# IC_Schema.net
KiCad netlist of a schematic drawn in Altium Designer
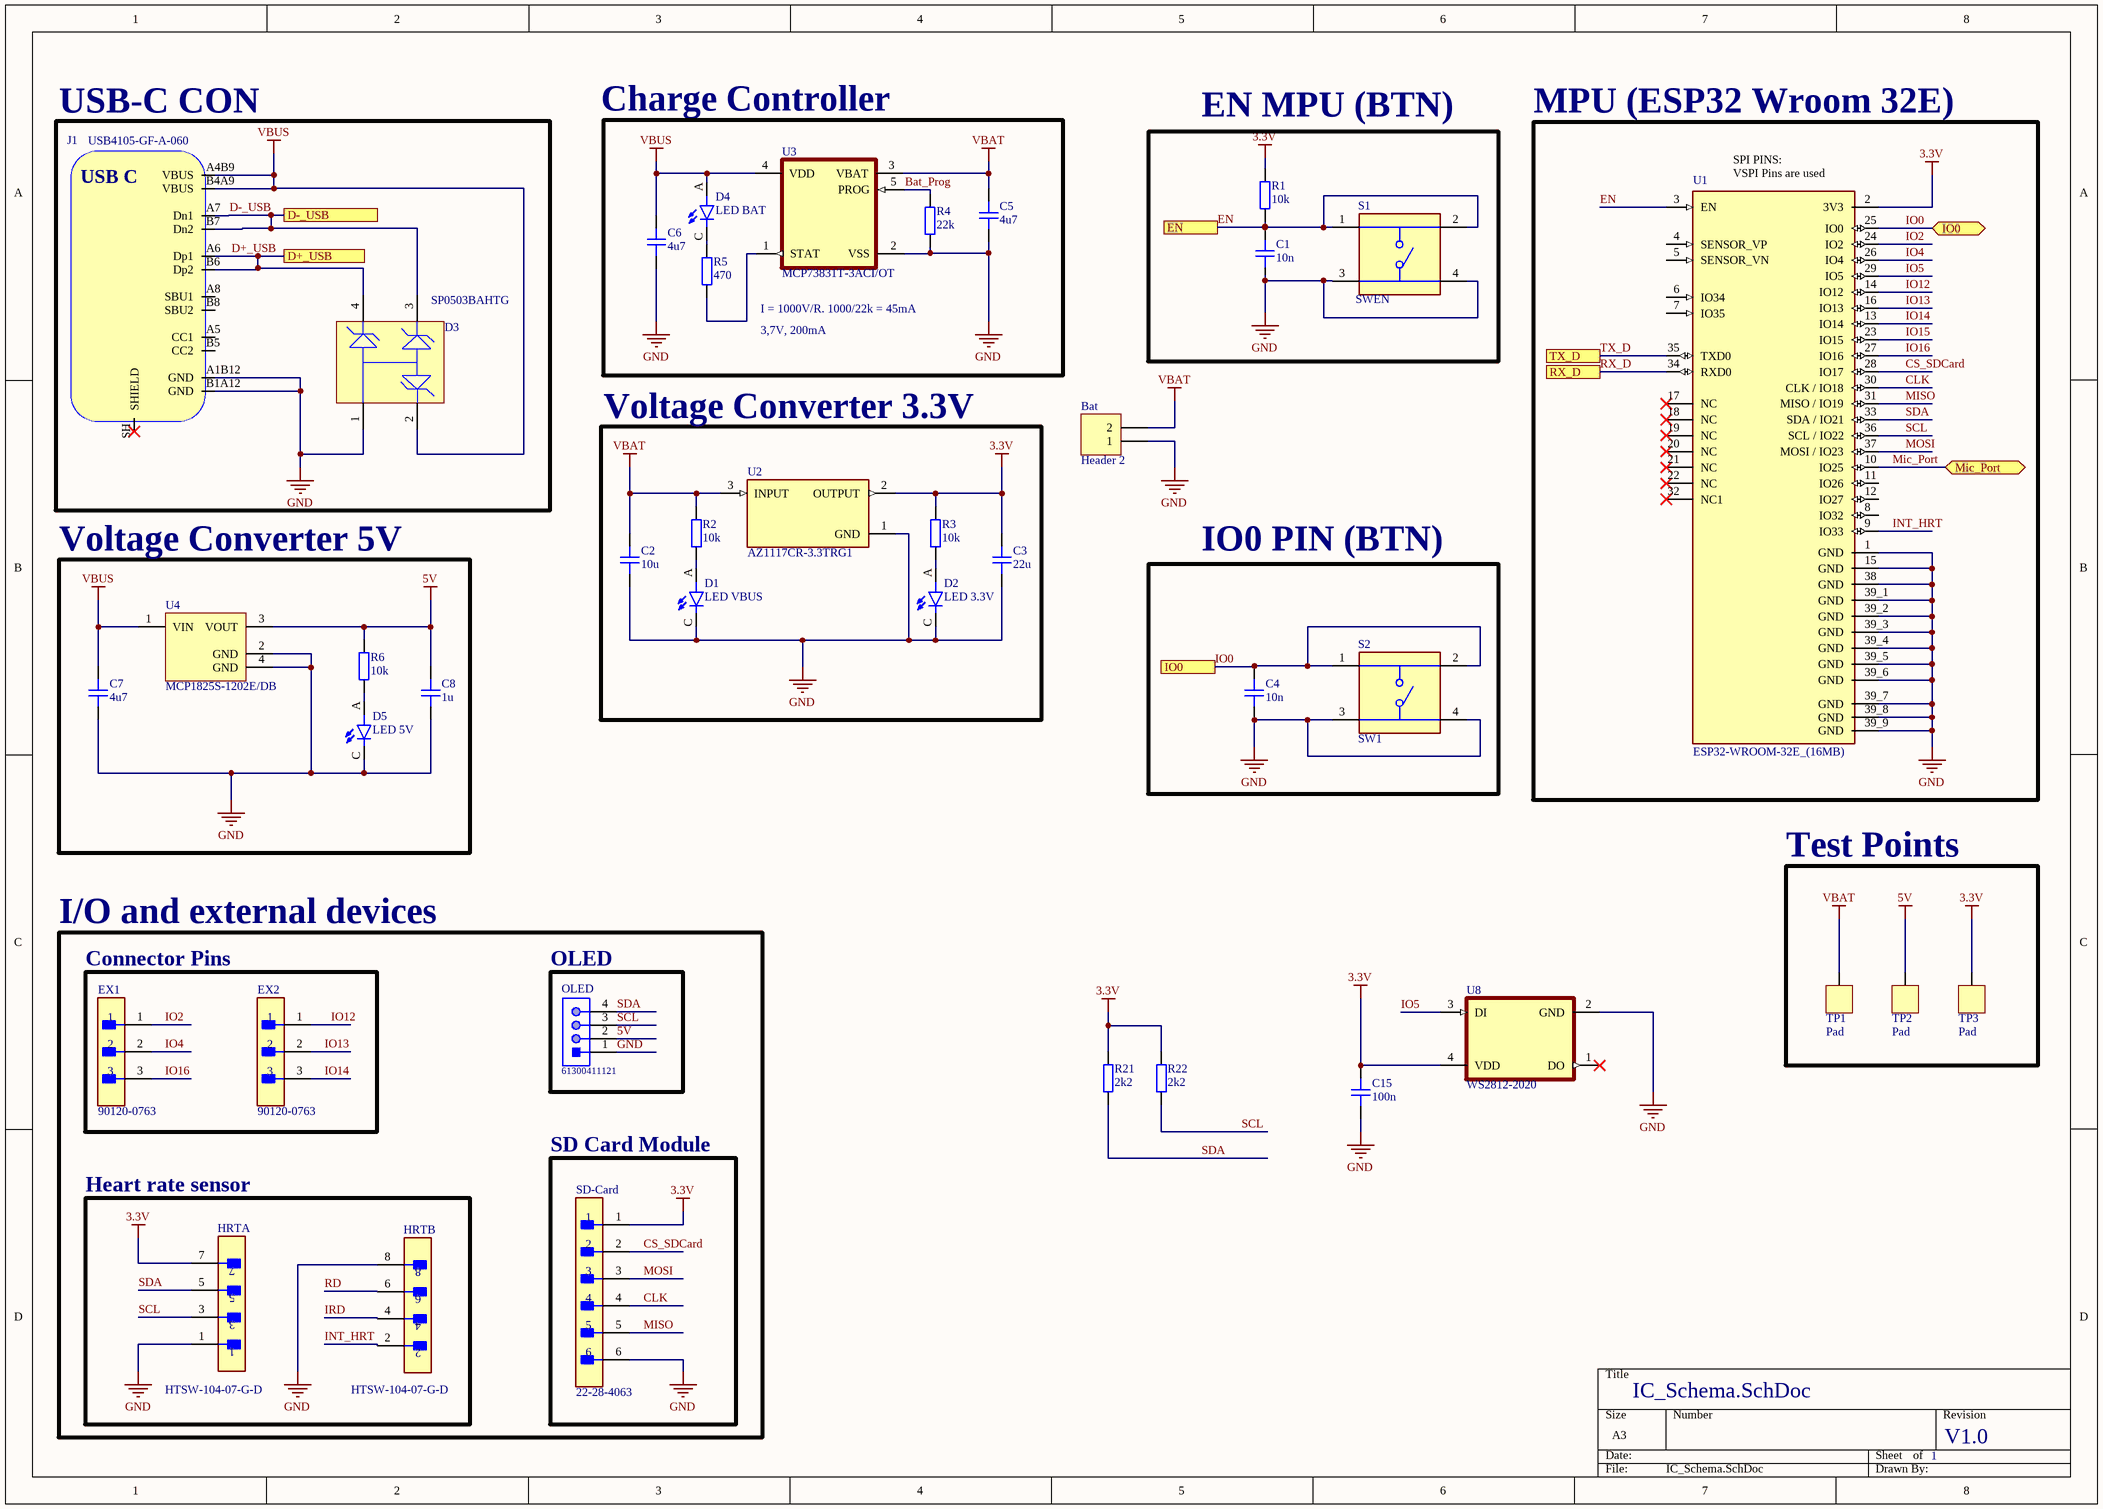
[diagram p0: IC_Schema.SchDoc]

(export (version "E")
  (design (tool "Eeschema 10.0.6"))
  (components
    (comp (ref "Bat")
      (value "Header 2")
      (footprint "HDR1X2")
      (description "Header, 2-Pin")
      (fields (field (name "PUBLISHER") "Altium Limited"))
      (libsource (lib "Miscellaneous Connectors") (part "Header 2"))
    )
    (comp (ref "C1")
      (value "10n")
      (footprint "CAP_1206")
      (description "Capacitor SMD 1206 50V")
      (libsource (lib "Schem_Lib_DaanHeetkamp.") (part "CAP_1206_50V"))
    )
    (comp (ref "C2")
      (value "10u")
      (footprint "CAP_1206")
      (description "Capacitor SMD 1206 50V")
      (libsource (lib "Schem_Lib_DaanHeetkamp.") (part "CAP_1206_50V"))
    )
    (comp (ref "C3")
      (value "22u")
      (footprint "CAP_1206")
      (description "Capacitor SMD 1206 50V")
      (libsource (lib "Schem_Lib_DaanHeetkamp.") (part "CAP_1206_50V"))
    )
    (comp (ref "C4")
      (value "10n")
      (footprint "CAP_1206")
      (description "Capacitor SMD 1206 50V")
      (libsource (lib "Schem_Lib_DaanHeetkamp.") (part "CAP_1206_50V"))
    )
    (comp (ref "C5")
      (value "4u7")
      (footprint "CAP_1206")
      (description "Capacitor SMD 1206 50V")
      (libsource (lib "Schem_Lib_DaanHeetkamp.") (part "CAP_1206_50V"))
    )
    (comp (ref "C6")
      (value "4u7")
      (footprint "CAP_1206")
      (description "Capacitor SMD 1206 50V")
      (libsource (lib "Schem_Lib_DaanHeetkamp.") (part "CAP_1206_50V"))
    )
    (comp (ref "C7")
      (value "4u7")
      (footprint "CAP_1206")
      (description "Capacitor SMD 1206 50V")
      (libsource (lib "Schem_Lib_DaanHeetkamp.") (part "CAP_1206_50V"))
    )
    (comp (ref "C8")
      (value "1u")
      (footprint "CAP_1206")
      (description "Capacitor SMD 1206 50V")
      (libsource (lib "Schem_Lib_DaanHeetkamp.") (part "CAP_1206_50V"))
    )
    (comp (ref "C15")
      (value "100n")
      (footprint "CAP_1206")
      (description "Capacitor SMD 1206 50V")
      (libsource (lib "Schem_Lib_DaanHeetkamp.") (part "CAP_1206_50V"))
    )
    (comp (ref "D1")
      (value "LED VBUS")
      (footprint "PCB_Lib_DaanHeetkamp:LED_1206")
      (description "Yellow 587nm LED Indication - Discrete 2V 1206 _3216 Metric_")
      (fields (field (name "MF") "Lite-On Inc.") (field (name "MP") "LTST-C230KSKT"))
      (libsource (lib "Schem_Lib_DaanHeetkamp.") (part "LED - 1206"))
    )
    (comp (ref "D2")
      (value "LED 3.3V")
      (footprint "PCB_Lib_DaanHeetkamp:LED_1206")
      (description "Yellow 587nm LED Indication - Discrete 2V 1206 _3216 Metric_")
      (fields (field (name "MF") "Lite-On Inc.") (field (name "MP") "LTST-C230KSKT"))
      (libsource (lib "Schem_Lib_DaanHeetkamp.") (part "LED - 1206"))
    )
    (comp (ref "D3")
      (value "SP0503BAHTG")
      (footprint "LFUS-SOT143-4_V")
      (description "TVS Diode Array, 30 pF, 30 KV, -40 to 85 degC, 4-Pin SOT143, RoHS, Tape and Reel")
      (fields (field (name "MANUFACTURER") "Littelfuse"))
      (libsource (lib "Altium Content Vault") (part "LFUS-SP0503BAHTG-SOT143-4"))
    )
    (comp (ref "D4")
      (value "LED BAT")
      (footprint "PCB_Lib_DaanHeetkamp:LED_1206")
      (description "Yellow 587nm LED Indication - Discrete 2V 1206 _3216 Metric_")
      (fields (field (name "MF") "Lite-On Inc.") (field (name "MP") "LTST-C230KSKT"))
      (libsource (lib "Schem_Lib_DaanHeetkamp.") (part "LED - 1206"))
    )
    (comp (ref "D5")
      (value "LED 5V")
      (footprint "PCB_Lib_DaanHeetkamp:LED_1206")
      (description "Yellow 587nm LED Indication - Discrete 2V 1206 _3216 Metric_")
      (fields (field (name "MF") "Lite-On Inc.") (field (name "MP") "LTST-C230KSKT"))
      (libsource (lib "Schem_Lib_DaanHeetkamp.") (part "LED - 1206"))
    )
    (comp (ref "EX1")
      (value "90120-0763")
      (footprint "FP-90120-0763-MFG")
      (description "CONN HEADER VERT 3POS 2.54MM")
      (fields
        (field (name "MANUFACTURER") "Molex")
        (field (name "OCTOPART") "https://octopart.com/90120-0763-molex-655433")
      )
      (libsource (lib "Altium Content Vault") (part "0d3f023dd272f625e17a2be33dea85f"))
    )
    (comp (ref "EX2")
      (value "90120-0763")
      (footprint "FP-90120-0763-MFG")
      (description "CONN HEADER VERT 3POS 2.54MM")
      (fields
        (field (name "MANUFACTURER") "Molex")
        (field (name "OCTOPART") "https://octopart.com/90120-0763-molex-655433")
      )
      (libsource (lib "Altium Content Vault") (part "0d3f023dd272f625e17a2be33dea85f"))
    )
    (comp (ref "HRT")
      (value "HTSW-104-07-G-D")
      (footprint "FP-HTSW-104-07-G-D-MFG")
      (description "CONN HEADER VERT 8POS 2.54MM")
      (fields
        (field (name "MANUFACTURER") "Samtec")
        (field (name "OCTOPART") "https://octopart.com/htsw-104-07-g-d-samtec-10613822")
      )
      (libsource (lib "Altium Content Vault") (part "811e954b9c034aa737de4d9295cbe7e"))
    )
    (comp (ref "J1")
      (value "USB4105-GF-A-060")
      (footprint "USB4105-GF-A-060")
      (description "USB Connector Type C SMT 12 Pin")
      (fields (field (name "MANUFACTURER") "GCT"))
      (libsource (lib "Schem_Lib_DaanHeetkamp.") (part "USB4105-GF-A-060"))
    )
    (comp (ref "OLED")
      (value "61300411121")
      (footprint "61300411121")
      (description "THT Vertical Pin Header WR-PHD, Pitch 2.54 mm, Single Row, 4 pins")
      (fields (field (name "MANUFACTURER") "Wurth Elektronik") (field (name "PUBLISHER") "WurthElektronik"))
      (libsource (lib "Altium Content Vault") (part "WE-CN-1P-M-R4"))
    )
    (comp (ref "R1")
      (value "10k")
      (footprint "RES_1206")
      (description "Resistor SMD 1206")
      (libsource (lib "Schem_Lib_DaanHeetkamp.") (part "RES_1206"))
    )
    (comp (ref "R2")
      (value "10k")
      (footprint "RES_1206")
      (description "Resistor SMD 1206")
      (libsource (lib "Schem_Lib_DaanHeetkamp.") (part "RES_1206"))
    )
    (comp (ref "R3")
      (value "10k")
      (footprint "RES_1206")
      (description "Resistor SMD 1206")
      (libsource (lib "Schem_Lib_DaanHeetkamp.") (part "RES_1206"))
    )
    (comp (ref "R4")
      (value "22k")
      (footprint "RES_1206")
      (description "Resistor SMD 1206")
      (libsource (lib "Schem_Lib_DaanHeetkamp.") (part "RES_1206"))
    )
    (comp (ref "R5")
      (value "470")
      (footprint "RES_1206")
      (description "Resistor SMD 1206")
      (libsource (lib "Schem_Lib_DaanHeetkamp.") (part "RES_1206"))
    )
    (comp (ref "R6")
      (value "10k")
      (footprint "RES_1206")
      (description "Resistor SMD 1206")
      (libsource (lib "Schem_Lib_DaanHeetkamp.") (part "RES_1206"))
    )
    (comp (ref "R21")
      (value "2k2")
      (footprint "RES_1206")
      (description "Resistor SMD 1206")
      (libsource (lib "Schem_Lib_DaanHeetkamp.") (part "RES_1206"))
    )
    (comp (ref "R22")
      (value "2k2")
      (footprint "RES_1206")
      (description "Resistor SMD 1206")
      (libsource (lib "Schem_Lib_DaanHeetkamp.") (part "RES_1206"))
    )
    (comp (ref "S1")
      (value "SWEN")
      (footprint "Switch/Button 4 Pin Through Hole")
      (fields (field (name "MP") "TS02-66-120-BK-260-LCR-D") (field (name "MF") "CUI Devices"))
      (libsource (lib "Schem_Lib_DaanHeetkamp") (part "Switch/Button 4 Pin Through Hole"))
    )
    (comp (ref "S2")
      (value "SW1")
      (footprint "Switch/Button 4 Pin Through Hole")
      (fields (field (name "MP") "TS02-66-120-BK-260-LCR-D") (field (name "MF") "CUI Devices"))
      (libsource (lib "Schem_Lib_DaanHeetkamp") (part "Switch/Button 4 Pin Through Hole"))
    )
    (comp (ref "SD-Card")
      (value "22-28-4063")
      (footprint "FP-22-28-4063-MFG")
      (description "CONN HEADER VERT 6POS 2.54MM")
      (libsource (lib "Altium Content Vault") (part "f2cb566baf1c37ab5a3b8e90bbeafd6"))
    )
    (comp (ref "TP1")
      (value "Pad")
      (footprint "PAD_SQ_2MM")
      (description "Test Point Square 2mm")
      (libsource (lib "Schem_Lib_DaanHeetkamp.") (part "PAD_SQ_2MM"))
    )
    (comp (ref "TP2")
      (value "Pad")
      (footprint "PAD_SQ_2MM")
      (description "Test Point Square 2mm")
      (libsource (lib "Schem_Lib_DaanHeetkamp.") (part "PAD_SQ_2MM"))
    )
    (comp (ref "TP3")
      (value "Pad")
      (footprint "PAD_SQ_2MM")
      (description "Test Point Square 2mm")
      (libsource (lib "Schem_Lib_DaanHeetkamp.") (part "PAD_SQ_2MM"))
    )
    (comp (ref "U1")
      (value "ESP32-WROOM-32E_(16MB)")
      (footprint "XCVR_ESP32-WROOM-32E_(16MB)")
      (fields (field (name "MP") "ESP32-WROOM-32E (16MB)") (field (name "MF") "Espressif Systems"))
      (libsource (lib "Schem_Lib_DaanHeetkamp.") (part "ESP32-WROOM-32E_(16MB)"))
    )
    (comp (ref "U2")
      (value "AZ1117CR-3.3TRG1")
      (footprint "FP-SOT89-MFG")
      (description "IC REG LINEAR 3.3V 800MA SOT89")
      (fields
        (field (name "OCTOPART") "https://octopart.com/az1117cr-3.3trg1-diodes+inc.-30954805")
        (field (name "MANUFACTURER") "Diodes Inc.")
      )
      (libsource (lib "Altium Content Vault") (part "80dc4d5e0c5bf011f486f511683fde3"))
    )
    (comp (ref "U3")
      (value "MCP73831T-3ACI/OT")
      (footprint "PCB_Lib_DaanHeetkamp:SOT95P270X145-5N")
      (description "Charger IC Lithium Ion/Polymer SOT-23-5")
      (fields (field (name "MF") "Microchip"))
      (libsource (lib "Schem_Lib_DaanHeetkamp") (part "MCP73831T-3ACI/OT"))
    )
    (comp (ref "U4")
      (value "MCP1825S-1202E/DB")
      (footprint "SOT-223-DB3_N")
      (description "500 mA, Low Voltage, Low Quiescent Current LDO Regulator, 3-Pin SOT-223, Extended Temperature")
      (libsource (lib "Altium Content Vault") (part "PM-LINEREG-MCP1825-IL4"))
    )
    (comp (ref "U8")
      (value "WS2812-2020")
      (footprint "PCB_Lib_DaanHeetkamp:LED_WS2812-2020")
      (description "Intelligent control LED integrated light source")
      (libsource (lib "Schem_Lib_DaanHeetkamp.") (part "WS2812-2020"))
    )
  )
  (nets
    (net (code "1") (name "/Bat_Prog") (class "Default")
      (node (ref "R4") (pin "2") (pinfunction "2_2") (pintype "passive"))
      (node (ref "U3") (pin "5") (pinfunction "PROG_5") (pintype "input"))
    )
    (net (code "2") (name "/CLK") (class "Default")
      (node (ref "SD-Card") (pin "4") (pinfunction "4_4") (pintype "passive"))
      (node (ref "U1") (pin "30") (pinfunction "CLK_/_IO18_30") (pintype "bidirectional"))
    )
    (net (code "3") (name "/CS_SDCard") (class "Default")
      (node (ref "SD-Card") (pin "2") (pinfunction "2_2") (pintype "passive"))
      (node (ref "U1") (pin "28") (pinfunction "IO17_28") (pintype "bidirectional"))
    )
    (net (code "4") (name "/D+_USB") (class "Default")
      (node (ref "D3") (pin "4") (pinfunction "4_4") (pintype "passive"))
      (node (ref "J1") (pin "A6") (pinfunction "Dp1_A6") (pintype "passive"))
      (node (ref "J1") (pin "B6") (pinfunction "Dp2_B6") (pintype "passive"))
    )
    (net (code "5") (name "/D-_USB") (class "Default")
      (node (ref "D3") (pin "3") (pinfunction "3_3") (pintype "passive"))
      (node (ref "J1") (pin "A7") (pinfunction "Dn1_A7") (pintype "passive"))
      (node (ref "J1") (pin "B7") (pinfunction "Dn2_B7") (pintype "passive"))
    )
    (net (code "6") (name "/EN") (class "Default")
      (node (ref "C1") (pin "2") (pinfunction "2_2") (pintype "passive"))
      (node (ref "R1") (pin "2") (pinfunction "2_2") (pintype "passive"))
      (node (ref "S1") (pin "1") (pinfunction "1_1") (pintype "passive"))
      (node (ref "S1") (pin "2") (pinfunction "2_2") (pintype "passive"))
      (node (ref "U1") (pin "3") (pinfunction "EN_3") (pintype "input"))
    )
    (net (code "7") (name "/INT_HRT") (class "Default")
      (node (ref "HRT") (pin "2") (pinfunction "2_2") (pintype "passive"))
      (node (ref "U1") (pin "9") (pinfunction "IO33_9") (pintype "bidirectional"))
    )
    (net (code "8") (name "/IO0") (class "Default")
      (node (ref "C4") (pin "2") (pinfunction "2_2") (pintype "passive"))
      (node (ref "S2") (pin "1") (pinfunction "1_1") (pintype "passive"))
      (node (ref "S2") (pin "2") (pinfunction "2_2") (pintype "passive"))
      (node (ref "U1") (pin "25") (pinfunction "IO0_25") (pintype "bidirectional"))
    )
    (net (code "9") (name "/IO2") (class "Default")
      (node (ref "EX1") (pin "1") (pinfunction "1_1") (pintype "passive"))
      (node (ref "U1") (pin "24") (pinfunction "IO2_24") (pintype "bidirectional"))
    )
    (net (code "10") (name "/IO4") (class "Default")
      (node (ref "EX1") (pin "2") (pinfunction "2_2") (pintype "passive"))
      (node (ref "U1") (pin "26") (pinfunction "IO4_26") (pintype "bidirectional"))
    )
    (net (code "11") (name "/IO5") (class "Default")
      (node (ref "U1") (pin "29") (pinfunction "IO5_29") (pintype "bidirectional"))
      (node (ref "U8") (pin "3") (pinfunction "DI_3") (pintype "input"))
    )
    (net (code "12") (name "/IO12") (class "Default")
      (node (ref "EX2") (pin "1") (pinfunction "1_1") (pintype "passive"))
      (node (ref "U1") (pin "14") (pinfunction "IO12_14") (pintype "bidirectional"))
    )
    (net (code "13") (name "/IO13") (class "Default")
      (node (ref "EX2") (pin "2") (pinfunction "2_2") (pintype "passive"))
      (node (ref "U1") (pin "16") (pinfunction "IO13_16") (pintype "bidirectional"))
    )
    (net (code "14") (name "/IO14") (class "Default")
      (node (ref "EX2") (pin "3") (pinfunction "3_3") (pintype "passive"))
      (node (ref "U1") (pin "13") (pinfunction "IO14_13") (pintype "bidirectional"))
    )
    (net (code "15") (name "/IO15") (class "Default")
      (node (ref "U1") (pin "23") (pinfunction "IO15_23") (pintype "bidirectional"))
    )
    (net (code "16") (name "/IO16") (class "Default")
      (node (ref "EX1") (pin "3") (pinfunction "3_3") (pintype "passive"))
      (node (ref "U1") (pin "27") (pinfunction "IO16_27") (pintype "bidirectional"))
    )
    (net (code "17") (name "/IRD") (class "Default")
      (node (ref "HRT") (pin "4") (pinfunction "4_4") (pintype "passive"))
    )
    (net (code "18") (name "/MISO") (class "Default")
      (node (ref "SD-Card") (pin "5") (pinfunction "5_5") (pintype "passive"))
      (node (ref "U1") (pin "31") (pinfunction "MISO_/_IO19_31") (pintype "bidirectional"))
    )
    (net (code "19") (name "/MOSI") (class "Default")
      (node (ref "SD-Card") (pin "3") (pinfunction "3_3") (pintype "passive"))
      (node (ref "U1") (pin "37") (pinfunction "MOSI_/_IO23_37") (pintype "bidirectional"))
    )
    (net (code "20") (name "/Mic_Port") (class "Default")
      (node (ref "U1") (pin "10") (pinfunction "IO25_10") (pintype "bidirectional"))
    )
    (net (code "21") (name "/RD") (class "Default")
      (node (ref "HRT") (pin "6") (pinfunction "6_6") (pintype "passive"))
    )
    (net (code "22") (name "/RX_D") (class "Default")
      (node (ref "U1") (pin "34") (pinfunction "RXD0_34") (pintype "bidirectional"))
    )
    (net (code "23") (name "/SCL") (class "Default")
      (node (ref "HRT") (pin "3") (pinfunction "3_3") (pintype "passive"))
      (node (ref "OLED") (pin "3") (pinfunction "3_3") (pintype "passive"))
      (node (ref "R22") (pin "2") (pinfunction "2_2") (pintype "passive"))
      (node (ref "U1") (pin "36") (pinfunction "SCL_/_IO22_36") (pintype "bidirectional"))
    )
    (net (code "24") (name "/SDA") (class "Default")
      (node (ref "HRT") (pin "5") (pinfunction "5_5") (pintype "passive"))
      (node (ref "OLED") (pin "4") (pinfunction "4_4") (pintype "passive"))
      (node (ref "R21") (pin "2") (pinfunction "2_2") (pintype "passive"))
      (node (ref "U1") (pin "33") (pinfunction "SDA_/_IO21_33") (pintype "bidirectional"))
    )
    (net (code "25") (name "/TX_D") (class "Default")
      (node (ref "U1") (pin "35") (pinfunction "TXD0_35") (pintype "bidirectional"))
    )
    (net (code "26") (name "3.3V") (class "Default")
      (node (ref "C15") (pin "2") (pinfunction "2_2") (pintype "passive"))
      (node (ref "C3") (pin "2") (pinfunction "2_2") (pintype "passive"))
      (node (ref "HRT") (pin "7") (pinfunction "7_7") (pintype "passive"))
      (node (ref "R1") (pin "1") (pinfunction "1_1") (pintype "passive"))
      (node (ref "R21") (pin "1") (pinfunction "1_1") (pintype "passive"))
      (node (ref "R22") (pin "1") (pinfunction "1_1") (pintype "passive"))
      (node (ref "R3") (pin "2") (pinfunction "2_2") (pintype "passive"))
      (node (ref "SD-Card") (pin "1") (pinfunction "1_1") (pintype "passive"))
      (node (ref "TP3") (pin "1") (pinfunction "1_1") (pintype "passive"))
      (node (ref "U1") (pin "2") (pinfunction "3V3_2") (pintype "power_in"))
      (node (ref "U2") (pin "2") (pinfunction "OUTPUT_2") (pintype "output"))
      (node (ref "U8") (pin "4") (pinfunction "VDD_4") (pintype "power_in"))
    )
    (net (code "27") (name "5V") (class "Default")
      (node (ref "C8") (pin "2") (pinfunction "2_2") (pintype "passive"))
      (node (ref "OLED") (pin "2") (pinfunction "2_2") (pintype "passive"))
      (node (ref "R6") (pin "2") (pinfunction "2_2") (pintype "passive"))
      (node (ref "TP2") (pin "1") (pinfunction "1_1") (pintype "passive"))
      (node (ref "U4") (pin "3") (pinfunction "VOUT_3") (pintype "power_in"))
    )
    (net (code "28") (name "GND") (class "Default")
      (node (ref "Bat") (pin "1") (pinfunction "1_1") (pintype "passive"))
      (node (ref "C1") (pin "1") (pinfunction "1_1") (pintype "passive"))
      (node (ref "C15") (pin "1") (pinfunction "1_1") (pintype "passive"))
      (node (ref "C2") (pin "1") (pinfunction "1_1") (pintype "passive"))
      (node (ref "C3") (pin "1") (pinfunction "1_1") (pintype "passive"))
      (node (ref "C4") (pin "1") (pinfunction "1_1") (pintype "passive"))
      (node (ref "C5") (pin "1") (pinfunction "1_1") (pintype "passive"))
      (node (ref "C6") (pin "1") (pinfunction "1_1") (pintype "passive"))
      (node (ref "C7") (pin "1") (pinfunction "1_1") (pintype "passive"))
      (node (ref "C8") (pin "1") (pinfunction "1_1") (pintype "passive"))
      (node (ref "D1") (pin "C") (pinfunction "C_C") (pintype "passive"))
      (node (ref "D2") (pin "C") (pinfunction "C_C") (pintype "passive"))
      (node (ref "D3") (pin "1") (pinfunction "1_1") (pintype "passive"))
      (node (ref "D5") (pin "C") (pinfunction "C_C") (pintype "passive"))
      (node (ref "HRT") (pin "1") (pinfunction "1_1") (pintype "passive"))
      (node (ref "HRT") (pin "8") (pinfunction "8_8") (pintype "passive"))
      (node (ref "J1") (pin "A1B12") (pinfunction "GND_A1B12") (pintype "passive"))
      (node (ref "J1") (pin "B1A12") (pinfunction "GND_B1A12") (pintype "passive"))
      (node (ref "OLED") (pin "1") (pinfunction "1_1") (pintype "passive"))
      (node (ref "R4") (pin "1") (pinfunction "1_1") (pintype "passive"))
      (node (ref "S1") (pin "3") (pinfunction "3_3") (pintype "passive"))
      (node (ref "S1") (pin "4") (pinfunction "4_4") (pintype "passive"))
      (node (ref "S2") (pin "3") (pinfunction "3_3") (pintype "passive"))
      (node (ref "S2") (pin "4") (pinfunction "4_4") (pintype "passive"))
      (node (ref "SD-Card") (pin "6") (pinfunction "6_6") (pintype "passive"))
      (node (ref "U1") (pin "1") (pinfunction "GND_1") (pintype "power_in"))
      (node (ref "U1") (pin "15") (pinfunction "GND_15") (pintype "power_in"))
      (node (ref "U1") (pin "38") (pinfunction "GND_38") (pintype "power_in"))
      (node (ref "U1") (pin "39_1") (pinfunction "GND_39_1") (pintype "power_in"))
      (node (ref "U1") (pin "39_2") (pinfunction "GND_39_2") (pintype "power_in"))
      (node (ref "U1") (pin "39_3") (pinfunction "GND_39_3") (pintype "power_in"))
      (node (ref "U1") (pin "39_4") (pinfunction "GND_39_4") (pintype "power_in"))
      (node (ref "U1") (pin "39_5") (pinfunction "GND_39_5") (pintype "power_in"))
      (node (ref "U1") (pin "39_6") (pinfunction "GND_39_6") (pintype "power_in"))
      (node (ref "U1") (pin "39_7") (pinfunction "GND_39_7") (pintype "power_in"))
      (node (ref "U1") (pin "39_8") (pinfunction "GND_39_8") (pintype "power_in"))
      (node (ref "U1") (pin "39_9") (pinfunction "GND_39_9") (pintype "power_in"))
      (node (ref "U2") (pin "1") (pinfunction "GND_1") (pintype "power_in"))
      (node (ref "U3") (pin "2") (pinfunction "VSS_2") (pintype "power_in"))
      (node (ref "U4") (pin "2") (pinfunction "GND_2") (pintype "power_in"))
      (node (ref "U4") (pin "4") (pinfunction "GND_4") (pintype "power_in"))
      (node (ref "U8") (pin "2") (pinfunction "GND_2") (pintype "power_in"))
    )
    (net (code "29") (name "Net-(D1-PadA)") (class "Default")
      (node (ref "D1") (pin "A") (pinfunction "A_A") (pintype "passive"))
      (node (ref "R2") (pin "1") (pinfunction "1_1") (pintype "passive"))
    )
    (net (code "30") (name "Net-(D2-PadA)") (class "Default")
      (node (ref "D2") (pin "A") (pinfunction "A_A") (pintype "passive"))
      (node (ref "R3") (pin "1") (pinfunction "1_1") (pintype "passive"))
    )
    (net (code "31") (name "Net-(D4-PadC)") (class "Default")
      (node (ref "D4") (pin "C") (pinfunction "C_C") (pintype "passive"))
      (node (ref "R5") (pin "2") (pinfunction "2_2") (pintype "passive"))
    )
    (net (code "32") (name "Net-(D5-PadA)") (class "Default")
      (node (ref "D5") (pin "A") (pinfunction "A_A") (pintype "passive"))
      (node (ref "R6") (pin "1") (pinfunction "1_1") (pintype "passive"))
    )
    (net (code "33") (name "Net-(U3-STAT)") (class "Default")
      (node (ref "R5") (pin "1") (pinfunction "1_1") (pintype "passive"))
      (node (ref "U3") (pin "1") (pinfunction "STAT_1") (pintype "output"))
    )
    (net (code "34") (name "VBAT") (class "Default")
      (node (ref "Bat") (pin "2") (pinfunction "2_2") (pintype "passive"))
      (node (ref "C2") (pin "2") (pinfunction "2_2") (pintype "passive"))
      (node (ref "C5") (pin "2") (pinfunction "2_2") (pintype "passive"))
      (node (ref "R2") (pin "2") (pinfunction "2_2") (pintype "passive"))
      (node (ref "TP1") (pin "1") (pinfunction "1_1") (pintype "passive"))
      (node (ref "U2") (pin "3") (pinfunction "INPUT_3") (pintype "input"))
      (node (ref "U3") (pin "3") (pinfunction "VBAT_3") (pintype "power_in"))
    )
    (net (code "35") (name "VBUS") (class "Default")
      (node (ref "C6") (pin "2") (pinfunction "2_2") (pintype "passive"))
      (node (ref "C7") (pin "2") (pinfunction "2_2") (pintype "passive"))
      (node (ref "D3") (pin "2") (pinfunction "2_2") (pintype "passive"))
      (node (ref "D4") (pin "A") (pinfunction "A_A") (pintype "passive"))
      (node (ref "J1") (pin "A4B9") (pinfunction "VBUS_A4B9") (pintype "passive"))
      (node (ref "J1") (pin "B4A9") (pinfunction "VBUS_B4A9") (pintype "passive"))
      (node (ref "U3") (pin "4") (pinfunction "VDD_4") (pintype "power_in"))
      (node (ref "U4") (pin "1") (pinfunction "VIN_1") (pintype "power_in"))
    )
    (net (code "36") (name "unconnected-(J1-CC1-PadA5)") (class "Default")
      (node (ref "J1") (pin "A5") (pinfunction "CC1_A5") (pintype "passive"))
    )
    (net (code "37") (name "unconnected-(J1-CC2-PadB5)") (class "Default")
      (node (ref "J1") (pin "B5") (pinfunction "CC2_B5") (pintype "passive"))
    )
    (net (code "38") (name "unconnected-(J1-SBU1-PadA8)") (class "Default")
      (node (ref "J1") (pin "A8") (pinfunction "SBU1_A8") (pintype "passive"))
    )
    (net (code "39") (name "unconnected-(J1-SBU2-PadB8)") (class "Default")
      (node (ref "J1") (pin "B8") (pinfunction "SBU2_B8") (pintype "passive"))
    )
    (net (code "40") (name "unconnected-(J1-SHIELD-PadSH)") (class "Default")
      (node (ref "J1") (pin "SH") (pinfunction "SHIELD_SH") (pintype "passive+no_connect"))
    )
    (net (code "41") (name "unconnected-(U1-IO26-Pad11)") (class "Default")
      (node (ref "U1") (pin "11") (pinfunction "IO26_11") (pintype "bidirectional"))
    )
    (net (code "42") (name "unconnected-(U1-IO27-Pad12)") (class "Default")
      (node (ref "U1") (pin "12") (pinfunction "IO27_12") (pintype "bidirectional"))
    )
    (net (code "43") (name "unconnected-(U1-IO32-Pad8)") (class "Default")
      (node (ref "U1") (pin "8") (pinfunction "IO32_8") (pintype "bidirectional"))
    )
    (net (code "44") (name "unconnected-(U1-IO34-Pad6)") (class "Default")
      (node (ref "U1") (pin "6") (pinfunction "IO34_6") (pintype "input"))
    )
    (net (code "45") (name "unconnected-(U1-IO35-Pad7)") (class "Default")
      (node (ref "U1") (pin "7") (pinfunction "IO35_7") (pintype "input"))
    )
    (net (code "46") (name "unconnected-(U1-NC-Pad17)") (class "Default")
      (node (ref "U1") (pin "17") (pinfunction "NC_17") (pintype "passive+no_connect"))
    )
    (net (code "47") (name "unconnected-(U1-NC-Pad18)") (class "Default")
      (node (ref "U1") (pin "18") (pinfunction "NC_18") (pintype "passive+no_connect"))
    )
    (net (code "48") (name "unconnected-(U1-NC-Pad19)") (class "Default")
      (node (ref "U1") (pin "19") (pinfunction "NC_19") (pintype "passive+no_connect"))
    )
    (net (code "49") (name "unconnected-(U1-NC-Pad20)") (class "Default")
      (node (ref "U1") (pin "20") (pinfunction "NC_20") (pintype "passive+no_connect"))
    )
    (net (code "50") (name "unconnected-(U1-NC-Pad21)") (class "Default")
      (node (ref "U1") (pin "21") (pinfunction "NC_21") (pintype "passive+no_connect"))
    )
    (net (code "51") (name "unconnected-(U1-NC-Pad22)") (class "Default")
      (node (ref "U1") (pin "22") (pinfunction "NC_22") (pintype "passive+no_connect"))
    )
    (net (code "52") (name "unconnected-(U1-NC1-Pad32)") (class "Default")
      (node (ref "U1") (pin "32") (pinfunction "NC1_32") (pintype "passive+no_connect"))
    )
    (net (code "53") (name "unconnected-(U1-SENSOR_VN-Pad5)") (class "Default")
      (node (ref "U1") (pin "5") (pinfunction "SENSOR_VN_5") (pintype "input"))
    )
    (net (code "54") (name "unconnected-(U1-SENSOR_VP-Pad4)") (class "Default")
      (node (ref "U1") (pin "4") (pinfunction "SENSOR_VP_4") (pintype "input"))
    )
    (net (code "55") (name "unconnected-(U8-DO-Pad1)") (class "Default")
      (node (ref "U8") (pin "1") (pinfunction "DO_1") (pintype "output+no_connect"))
    )
  )
)
